# GPIO_LED.net
KiCad netlist of a schematic drawn in Altium Designer
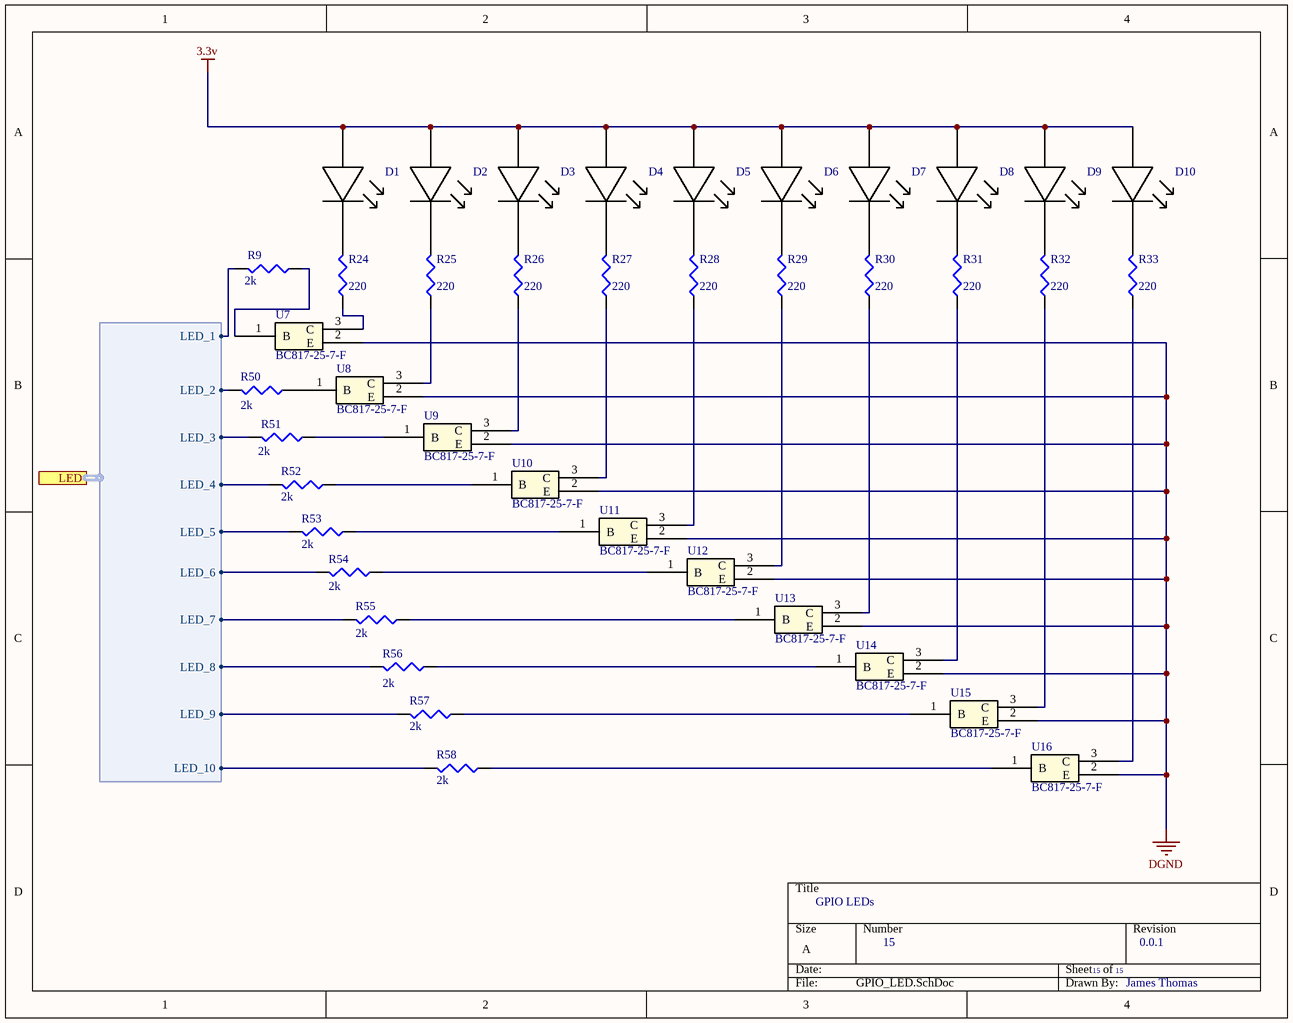
[diagram p0: GPIO_LED.SchDoc]

(export (version "E")
  (design (tool "Eeschema 10.0.6"))
  (components
    (comp (ref "D1")
      (value "LP T67F-P1R2-35-1-20-R18-Z")
      (footprint "LP T67F-P1R2-35-1-20-R18-Z")
      (description "SMD LED")
      (libsource (lib "Components") (part "LP T67F-P1R2-35-1-20-R18-Z"))
    )
    (comp (ref "D2")
      (value "LP T67F-P1R2-35-1-20-R18-Z")
      (footprint "LP T67F-P1R2-35-1-20-R18-Z")
      (description "SMD LED")
      (libsource (lib "Components") (part "LP T67F-P1R2-35-1-20-R18-Z"))
    )
    (comp (ref "D3")
      (value "LP T67F-P1R2-35-1-20-R18-Z")
      (footprint "LP T67F-P1R2-35-1-20-R18-Z")
      (description "SMD LED")
      (libsource (lib "Components") (part "LP T67F-P1R2-35-1-20-R18-Z"))
    )
    (comp (ref "D4")
      (value "LP T67F-P1R2-35-1-20-R18-Z")
      (footprint "LP T67F-P1R2-35-1-20-R18-Z")
      (description "SMD LED")
      (libsource (lib "Components") (part "LP T67F-P1R2-35-1-20-R18-Z"))
    )
    (comp (ref "D5")
      (value "LP T67F-P1R2-35-1-20-R18-Z")
      (footprint "LP T67F-P1R2-35-1-20-R18-Z")
      (description "SMD LED")
      (libsource (lib "Components") (part "LP T67F-P1R2-35-1-20-R18-Z"))
    )
    (comp (ref "D6")
      (value "LP T67F-P1R2-35-1-20-R18-Z")
      (footprint "LP T67F-P1R2-35-1-20-R18-Z")
      (description "SMD LED")
      (libsource (lib "Components") (part "LP T67F-P1R2-35-1-20-R18-Z"))
    )
    (comp (ref "D7")
      (value "LP T67F-P1R2-35-1-20-R18-Z")
      (footprint "LP T67F-P1R2-35-1-20-R18-Z")
      (description "SMD LED")
      (libsource (lib "Components") (part "LP T67F-P1R2-35-1-20-R18-Z"))
    )
    (comp (ref "D8")
      (value "LP T67F-P1R2-35-1-20-R18-Z")
      (footprint "LP T67F-P1R2-35-1-20-R18-Z")
      (description "SMD LED")
      (libsource (lib "Components") (part "LP T67F-P1R2-35-1-20-R18-Z"))
    )
    (comp (ref "D9")
      (value "LP T67F-P1R2-35-1-20-R18-Z")
      (footprint "LP T67F-P1R2-35-1-20-R18-Z")
      (description "SMD LED")
      (libsource (lib "Components") (part "LP T67F-P1R2-35-1-20-R18-Z"))
    )
    (comp (ref "D10")
      (value "LP T67F-P1R2-35-1-20-R18-Z")
      (footprint "LP T67F-P1R2-35-1-20-R18-Z")
      (description "SMD LED")
      (libsource (lib "Components") (part "LP T67F-P1R2-35-1-20-R18-Z"))
    )
    (comp (ref "R9")
      (value "2k")
      (footprint "J1-0603")
      (description "Resistor")
      (fields (field (name "Comment") "Res3") (field (name "PUBLISHER") "Altium Limited"))
      (libsource (lib "Miscellaneous Devices") (part "Res3"))
    )
    (comp (ref "R24")
      (value "220")
      (footprint "J1-0603")
      (description "Resistor")
      (fields (field (name "Comment") "Res3") (field (name "PUBLISHER") "Altium Limited"))
      (libsource (lib "Miscellaneous Devices") (part "Res3"))
    )
    (comp (ref "R25")
      (value "220")
      (footprint "J1-0603")
      (description "Resistor")
      (fields (field (name "Comment") "Res3") (field (name "PUBLISHER") "Altium Limited"))
      (libsource (lib "Miscellaneous Devices") (part "Res3"))
    )
    (comp (ref "R26")
      (value "220")
      (footprint "J1-0603")
      (description "Resistor")
      (fields (field (name "Comment") "Res3") (field (name "PUBLISHER") "Altium Limited"))
      (libsource (lib "Miscellaneous Devices") (part "Res3"))
    )
    (comp (ref "R27")
      (value "220")
      (footprint "J1-0603")
      (description "Resistor")
      (fields (field (name "Comment") "Res3") (field (name "PUBLISHER") "Altium Limited"))
      (libsource (lib "Miscellaneous Devices") (part "Res3"))
    )
    (comp (ref "R28")
      (value "220")
      (footprint "J1-0603")
      (description "Resistor")
      (fields (field (name "Comment") "Res3") (field (name "PUBLISHER") "Altium Limited"))
      (libsource (lib "Miscellaneous Devices") (part "Res3"))
    )
    (comp (ref "R29")
      (value "220")
      (footprint "J1-0603")
      (description "Resistor")
      (fields (field (name "Comment") "Res3") (field (name "PUBLISHER") "Altium Limited"))
      (libsource (lib "Miscellaneous Devices") (part "Res3"))
    )
    (comp (ref "R30")
      (value "220")
      (footprint "J1-0603")
      (description "Resistor")
      (fields (field (name "Comment") "Res3") (field (name "PUBLISHER") "Altium Limited"))
      (libsource (lib "Miscellaneous Devices") (part "Res3"))
    )
    (comp (ref "R31")
      (value "220")
      (footprint "J1-0603")
      (description "Resistor")
      (fields (field (name "Comment") "Res3") (field (name "PUBLISHER") "Altium Limited"))
      (libsource (lib "Miscellaneous Devices") (part "Res3"))
    )
    (comp (ref "R32")
      (value "220")
      (footprint "J1-0603")
      (description "Resistor")
      (fields (field (name "Comment") "Res3") (field (name "PUBLISHER") "Altium Limited"))
      (libsource (lib "Miscellaneous Devices") (part "Res3"))
    )
    (comp (ref "R33")
      (value "220")
      (footprint "J1-0603")
      (description "Resistor")
      (fields (field (name "Comment") "Res3") (field (name "PUBLISHER") "Altium Limited"))
      (libsource (lib "Miscellaneous Devices") (part "Res3"))
    )
    (comp (ref "R50")
      (value "2k")
      (footprint "J1-0603")
      (description "Resistor")
      (fields (field (name "Comment") "Res3") (field (name "PUBLISHER") "Altium Limited"))
      (libsource (lib "Miscellaneous Devices") (part "Res3"))
    )
    (comp (ref "R51")
      (value "2k")
      (footprint "J1-0603")
      (description "Resistor")
      (fields (field (name "Comment") "Res3") (field (name "PUBLISHER") "Altium Limited"))
      (libsource (lib "Miscellaneous Devices") (part "Res3"))
    )
    (comp (ref "R52")
      (value "2k")
      (footprint "J1-0603")
      (description "Resistor")
      (fields (field (name "Comment") "Res3") (field (name "PUBLISHER") "Altium Limited"))
      (libsource (lib "Miscellaneous Devices") (part "Res3"))
    )
    (comp (ref "R53")
      (value "2k")
      (footprint "J1-0603")
      (description "Resistor")
      (fields (field (name "Comment") "Res3") (field (name "PUBLISHER") "Altium Limited"))
      (libsource (lib "Miscellaneous Devices") (part "Res3"))
    )
    (comp (ref "R54")
      (value "2k")
      (footprint "J1-0603")
      (description "Resistor")
      (fields (field (name "Comment") "Res3") (field (name "PUBLISHER") "Altium Limited"))
      (libsource (lib "Miscellaneous Devices") (part "Res3"))
    )
    (comp (ref "R55")
      (value "2k")
      (footprint "J1-0603")
      (description "Resistor")
      (fields (field (name "Comment") "Res3") (field (name "PUBLISHER") "Altium Limited"))
      (libsource (lib "Miscellaneous Devices") (part "Res3"))
    )
    (comp (ref "R56")
      (value "2k")
      (footprint "J1-0603")
      (description "Resistor")
      (fields (field (name "Comment") "Res3") (field (name "PUBLISHER") "Altium Limited"))
      (libsource (lib "Miscellaneous Devices") (part "Res3"))
    )
    (comp (ref "R57")
      (value "2k")
      (footprint "J1-0603")
      (description "Resistor")
      (fields (field (name "Comment") "Res3") (field (name "PUBLISHER") "Altium Limited"))
      (libsource (lib "Miscellaneous Devices") (part "Res3"))
    )
    (comp (ref "R58")
      (value "2k")
      (footprint "J1-0603")
      (description "Resistor")
      (fields (field (name "Comment") "Res3") (field (name "PUBLISHER") "Altium Limited"))
      (libsource (lib "Miscellaneous Devices") (part "Res3"))
    )
    (comp (ref "U7")
      (value "BC817-25-7-F")
      (footprint "*SOT23")
      (description "NPN Transistor")
      (fields (field (name "COPYRIGHT") "Copyright (C) 2018 Accelerated Designs. All rights reserved"))
      (libsource (lib "Components") (part "BC817-25-7-F"))
    )
    (comp (ref "U8")
      (value "BC817-25-7-F")
      (footprint "*SOT23")
      (description "NPN Transistor")
      (fields (field (name "COPYRIGHT") "Copyright (C) 2018 Accelerated Designs. All rights reserved"))
      (libsource (lib "Components") (part "BC817-25-7-F"))
    )
    (comp (ref "U9")
      (value "BC817-25-7-F")
      (footprint "*SOT23")
      (description "NPN Transistor")
      (fields (field (name "COPYRIGHT") "Copyright (C) 2018 Accelerated Designs. All rights reserved"))
      (libsource (lib "Components") (part "BC817-25-7-F"))
    )
    (comp (ref "U10")
      (value "BC817-25-7-F")
      (footprint "*SOT23")
      (description "NPN Transistor")
      (fields (field (name "COPYRIGHT") "Copyright (C) 2018 Accelerated Designs. All rights reserved"))
      (libsource (lib "Components") (part "BC817-25-7-F"))
    )
    (comp (ref "U11")
      (value "BC817-25-7-F")
      (footprint "*SOT23")
      (description "NPN Transistor")
      (fields (field (name "COPYRIGHT") "Copyright (C) 2018 Accelerated Designs. All rights reserved"))
      (libsource (lib "Components") (part "BC817-25-7-F"))
    )
    (comp (ref "U12")
      (value "BC817-25-7-F")
      (footprint "*SOT23")
      (description "NPN Transistor")
      (fields (field (name "COPYRIGHT") "Copyright (C) 2018 Accelerated Designs. All rights reserved"))
      (libsource (lib "Components") (part "BC817-25-7-F"))
    )
    (comp (ref "U13")
      (value "BC817-25-7-F")
      (footprint "*SOT23")
      (description "NPN Transistor")
      (fields (field (name "COPYRIGHT") "Copyright (C) 2018 Accelerated Designs. All rights reserved"))
      (libsource (lib "Components") (part "BC817-25-7-F"))
    )
    (comp (ref "U14")
      (value "BC817-25-7-F")
      (footprint "*SOT23")
      (description "NPN Transistor")
      (fields (field (name "COPYRIGHT") "Copyright (C) 2018 Accelerated Designs. All rights reserved"))
      (libsource (lib "Components") (part "BC817-25-7-F"))
    )
    (comp (ref "U15")
      (value "BC817-25-7-F")
      (footprint "*SOT23")
      (description "NPN Transistor")
      (fields (field (name "COPYRIGHT") "Copyright (C) 2018 Accelerated Designs. All rights reserved"))
      (libsource (lib "Components") (part "BC817-25-7-F"))
    )
    (comp (ref "U16")
      (value "BC817-25-7-F")
      (footprint "*SOT23")
      (description "NPN Transistor")
      (fields (field (name "COPYRIGHT") "Copyright (C) 2018 Accelerated Designs. All rights reserved"))
      (libsource (lib "Components") (part "BC817-25-7-F"))
    )
  )
  (nets
    (net (code "2") (name "/LED_1") (class "Default")
      (node (ref "R9") (pin "2") (pinfunction "2_2") (pintype "passive"))
    )
    (net (code "3") (name "/LED_2") (class "Default")
      (node (ref "R50") (pin "2") (pinfunction "2_2") (pintype "passive"))
    )
    (net (code "4") (name "/LED_3") (class "Default")
      (node (ref "R51") (pin "2") (pinfunction "2_2") (pintype "passive"))
    )
    (net (code "5") (name "/LED_4") (class "Default")
      (node (ref "R52") (pin "2") (pinfunction "2_2") (pintype "passive"))
    )
    (net (code "6") (name "/LED_5") (class "Default")
      (node (ref "R53") (pin "2") (pinfunction "2_2") (pintype "passive"))
    )
    (net (code "7") (name "/LED_6") (class "Default")
      (node (ref "R54") (pin "2") (pinfunction "2_2") (pintype "passive"))
    )
    (net (code "8") (name "/LED_7") (class "Default")
      (node (ref "R55") (pin "2") (pinfunction "2_2") (pintype "passive"))
    )
    (net (code "9") (name "/LED_8") (class "Default")
      (node (ref "R56") (pin "2") (pinfunction "2_2") (pintype "passive"))
    )
    (net (code "10") (name "/LED_9") (class "Default")
      (node (ref "R57") (pin "2") (pinfunction "2_2") (pintype "passive"))
    )
    (net (code "11") (name "/LED_10") (class "Default")
      (node (ref "R58") (pin "2") (pinfunction "2_2") (pintype "passive"))
    )
    (net (code "13") (name "3.3v") (class "Default")
      (node (ref "D1") (pin "A") (pinfunction "A_A") (pintype "passive"))
      (node (ref "D10") (pin "A") (pinfunction "A_A") (pintype "passive"))
      (node (ref "D2") (pin "A") (pinfunction "A_A") (pintype "passive"))
      (node (ref "D3") (pin "A") (pinfunction "A_A") (pintype "passive"))
      (node (ref "D4") (pin "A") (pinfunction "A_A") (pintype "passive"))
      (node (ref "D5") (pin "A") (pinfunction "A_A") (pintype "passive"))
      (node (ref "D6") (pin "A") (pinfunction "A_A") (pintype "passive"))
      (node (ref "D7") (pin "A") (pinfunction "A_A") (pintype "passive"))
      (node (ref "D8") (pin "A") (pinfunction "A_A") (pintype "passive"))
      (node (ref "D9") (pin "A") (pinfunction "A_A") (pintype "passive"))
    )
    (net (code "14") (name "DGND") (class "Default")
      (node (ref "U10") (pin "2") (pinfunction "E_2") (pintype "passive"))
      (node (ref "U11") (pin "2") (pinfunction "E_2") (pintype "passive"))
      (node (ref "U12") (pin "2") (pinfunction "E_2") (pintype "passive"))
      (node (ref "U13") (pin "2") (pinfunction "E_2") (pintype "passive"))
      (node (ref "U14") (pin "2") (pinfunction "E_2") (pintype "passive"))
      (node (ref "U15") (pin "2") (pinfunction "E_2") (pintype "passive"))
      (node (ref "U16") (pin "2") (pinfunction "E_2") (pintype "passive"))
      (node (ref "U7") (pin "2") (pinfunction "E_2") (pintype "passive"))
      (node (ref "U8") (pin "2") (pinfunction "E_2") (pintype "passive"))
      (node (ref "U9") (pin "2") (pinfunction "E_2") (pintype "passive"))
    )
    (net (code "15") (name "Net-(D1-PadC)") (class "Default")
      (node (ref "D1") (pin "C") (pinfunction "C_C") (pintype "passive"))
      (node (ref "R24") (pin "2") (pinfunction "2_2") (pintype "passive"))
    )
    (net (code "16") (name "Net-(D2-PadC)") (class "Default")
      (node (ref "D2") (pin "C") (pinfunction "C_C") (pintype "passive"))
      (node (ref "R25") (pin "2") (pinfunction "2_2") (pintype "passive"))
    )
    (net (code "17") (name "Net-(D3-PadC)") (class "Default")
      (node (ref "D3") (pin "C") (pinfunction "C_C") (pintype "passive"))
      (node (ref "R26") (pin "2") (pinfunction "2_2") (pintype "passive"))
    )
    (net (code "18") (name "Net-(D4-PadC)") (class "Default")
      (node (ref "D4") (pin "C") (pinfunction "C_C") (pintype "passive"))
      (node (ref "R27") (pin "2") (pinfunction "2_2") (pintype "passive"))
    )
    (net (code "19") (name "Net-(D5-PadC)") (class "Default")
      (node (ref "D5") (pin "C") (pinfunction "C_C") (pintype "passive"))
      (node (ref "R28") (pin "2") (pinfunction "2_2") (pintype "passive"))
    )
    (net (code "20") (name "Net-(D6-PadC)") (class "Default")
      (node (ref "D6") (pin "C") (pinfunction "C_C") (pintype "passive"))
      (node (ref "R29") (pin "2") (pinfunction "2_2") (pintype "passive"))
    )
    (net (code "21") (name "Net-(D7-PadC)") (class "Default")
      (node (ref "D7") (pin "C") (pinfunction "C_C") (pintype "passive"))
      (node (ref "R30") (pin "2") (pinfunction "2_2") (pintype "passive"))
    )
    (net (code "22") (name "Net-(D8-PadC)") (class "Default")
      (node (ref "D8") (pin "C") (pinfunction "C_C") (pintype "passive"))
      (node (ref "R31") (pin "2") (pinfunction "2_2") (pintype "passive"))
    )
    (net (code "23") (name "Net-(D9-PadC)") (class "Default")
      (node (ref "D9") (pin "C") (pinfunction "C_C") (pintype "passive"))
      (node (ref "R32") (pin "2") (pinfunction "2_2") (pintype "passive"))
    )
    (net (code "24") (name "Net-(D10-PadC)") (class "Default")
      (node (ref "D10") (pin "C") (pinfunction "C_C") (pintype "passive"))
      (node (ref "R33") (pin "2") (pinfunction "2_2") (pintype "passive"))
    )
    (net (code "25") (name "Net-(U7-B)") (class "Default")
      (node (ref "R9") (pin "1") (pinfunction "1_1") (pintype "passive"))
      (node (ref "U7") (pin "1") (pinfunction "B_1") (pintype "passive"))
    )
    (net (code "26") (name "Net-(U7-C)") (class "Default")
      (node (ref "R24") (pin "1") (pinfunction "1_1") (pintype "passive"))
      (node (ref "U7") (pin "3") (pinfunction "C_3") (pintype "passive"))
    )
    (net (code "27") (name "Net-(U8-B)") (class "Default")
      (node (ref "R50") (pin "1") (pinfunction "1_1") (pintype "passive"))
      (node (ref "U8") (pin "1") (pinfunction "B_1") (pintype "passive"))
    )
    (net (code "28") (name "Net-(U8-C)") (class "Default")
      (node (ref "R25") (pin "1") (pinfunction "1_1") (pintype "passive"))
      (node (ref "U8") (pin "3") (pinfunction "C_3") (pintype "passive"))
    )
    (net (code "29") (name "Net-(U9-B)") (class "Default")
      (node (ref "R51") (pin "1") (pinfunction "1_1") (pintype "passive"))
      (node (ref "U9") (pin "1") (pinfunction "B_1") (pintype "passive"))
    )
    (net (code "30") (name "Net-(U9-C)") (class "Default")
      (node (ref "R26") (pin "1") (pinfunction "1_1") (pintype "passive"))
      (node (ref "U9") (pin "3") (pinfunction "C_3") (pintype "passive"))
    )
    (net (code "31") (name "Net-(U10-B)") (class "Default")
      (node (ref "R52") (pin "1") (pinfunction "1_1") (pintype "passive"))
      (node (ref "U10") (pin "1") (pinfunction "B_1") (pintype "passive"))
    )
    (net (code "32") (name "Net-(U10-C)") (class "Default")
      (node (ref "R27") (pin "1") (pinfunction "1_1") (pintype "passive"))
      (node (ref "U10") (pin "3") (pinfunction "C_3") (pintype "passive"))
    )
    (net (code "33") (name "Net-(U11-B)") (class "Default")
      (node (ref "R53") (pin "1") (pinfunction "1_1") (pintype "passive"))
      (node (ref "U11") (pin "1") (pinfunction "B_1") (pintype "passive"))
    )
    (net (code "34") (name "Net-(U11-C)") (class "Default")
      (node (ref "R28") (pin "1") (pinfunction "1_1") (pintype "passive"))
      (node (ref "U11") (pin "3") (pinfunction "C_3") (pintype "passive"))
    )
    (net (code "35") (name "Net-(U12-B)") (class "Default")
      (node (ref "R54") (pin "1") (pinfunction "1_1") (pintype "passive"))
      (node (ref "U12") (pin "1") (pinfunction "B_1") (pintype "passive"))
    )
    (net (code "36") (name "Net-(U12-C)") (class "Default")
      (node (ref "R29") (pin "1") (pinfunction "1_1") (pintype "passive"))
      (node (ref "U12") (pin "3") (pinfunction "C_3") (pintype "passive"))
    )
    (net (code "37") (name "Net-(U13-B)") (class "Default")
      (node (ref "R55") (pin "1") (pinfunction "1_1") (pintype "passive"))
      (node (ref "U13") (pin "1") (pinfunction "B_1") (pintype "passive"))
    )
    (net (code "38") (name "Net-(U13-C)") (class "Default")
      (node (ref "R30") (pin "1") (pinfunction "1_1") (pintype "passive"))
      (node (ref "U13") (pin "3") (pinfunction "C_3") (pintype "passive"))
    )
    (net (code "39") (name "Net-(U14-B)") (class "Default")
      (node (ref "R56") (pin "1") (pinfunction "1_1") (pintype "passive"))
      (node (ref "U14") (pin "1") (pinfunction "B_1") (pintype "passive"))
    )
    (net (code "40") (name "Net-(U14-C)") (class "Default")
      (node (ref "R31") (pin "1") (pinfunction "1_1") (pintype "passive"))
      (node (ref "U14") (pin "3") (pinfunction "C_3") (pintype "passive"))
    )
    (net (code "41") (name "Net-(U15-B)") (class "Default")
      (node (ref "R57") (pin "1") (pinfunction "1_1") (pintype "passive"))
      (node (ref "U15") (pin "1") (pinfunction "B_1") (pintype "passive"))
    )
    (net (code "42") (name "Net-(U15-C)") (class "Default")
      (node (ref "R32") (pin "1") (pinfunction "1_1") (pintype "passive"))
      (node (ref "U15") (pin "3") (pinfunction "C_3") (pintype "passive"))
    )
    (net (code "43") (name "Net-(U16-B)") (class "Default")
      (node (ref "R58") (pin "1") (pinfunction "1_1") (pintype "passive"))
      (node (ref "U16") (pin "1") (pinfunction "B_1") (pintype "passive"))
    )
    (net (code "44") (name "Net-(U16-C)") (class "Default")
      (node (ref "R33") (pin "1") (pinfunction "1_1") (pintype "passive"))
      (node (ref "U16") (pin "3") (pinfunction "C_3") (pintype "passive"))
    )
  )
)
